# RGB_LED_Board.net
KiCad netlist of a schematic drawn in EAGLE
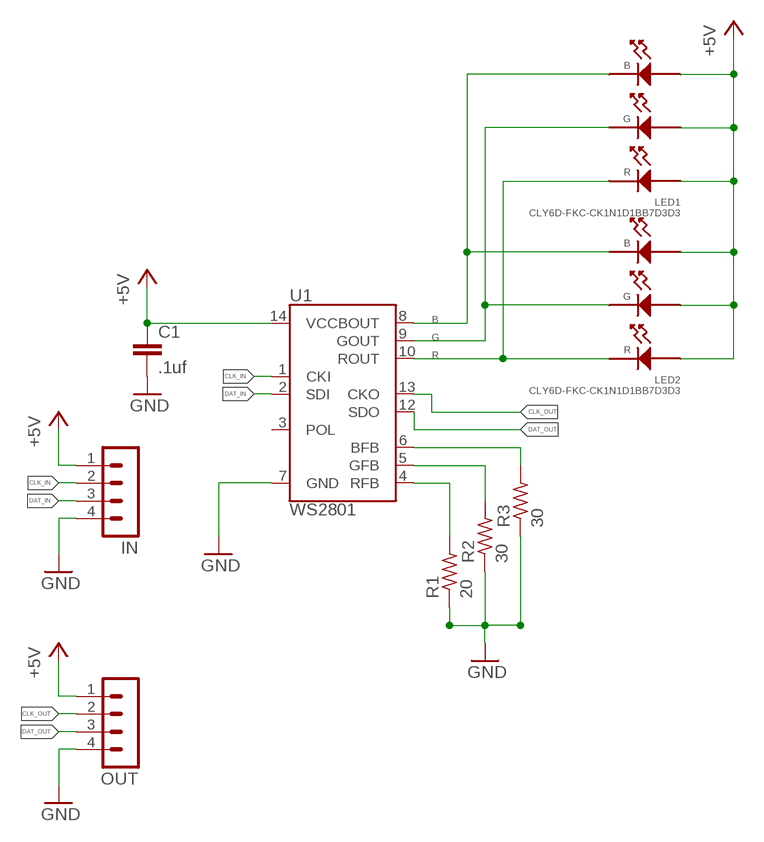
[diagram p0: schematic, sheet 1]

(export (version "E")
  (design (tool "Eeschema 10.0.6"))
  (components
    (comp (ref "C1")
      (value ".1uf")
      (footprint "eagle-import:0805")
      (libsource (lib "eagle-import") (part "CAP0805"))
    )
    (comp (ref "IN")
      (value "MA04-1")
      (footprint "eagle-import:MA04-1")
      (libsource (lib "eagle-import") (part "MA04-1"))
    )
    (comp (ref "LED1")
      (value "CLY6D-FKC-CK1N1D1BB7D3D3")
      (footprint "eagle-import:CLY6D-FKC")
      (libsource (lib "eagle-import") (part "CLY6D-FKC"))
    )
    (comp (ref "LED2")
      (value "CLY6D-FKC-CK1N1D1BB7D3D3")
      (footprint "eagle-import:CLY6D-FKC")
      (libsource (lib "eagle-import") (part "CLY6D-FKC"))
    )
    (comp (ref "OUT")
      (value "MA04-1")
      (footprint "eagle-import:MA04-1")
      (libsource (lib "eagle-import") (part "MA04-1"))
    )
    (comp (ref "R1")
      (value "20")
      (footprint "eagle-import:R0805")
      (libsource (lib "eagle-import") (part "R-US_R0805"))
    )
    (comp (ref "R2")
      (value "30")
      (footprint "eagle-import:R0805")
      (libsource (lib "eagle-import") (part "R-US_R0805"))
    )
    (comp (ref "R3")
      (value "30")
      (footprint "eagle-import:R0805")
      (libsource (lib "eagle-import") (part "R-US_R0805"))
    )
    (comp (ref "U1")
      (value "WS2801")
      (footprint "eagle-import:SOP-14")
      (libsource (lib "eagle-import") (part "WS2801"))
    )
  )
  (nets
    (net (code "1") (name "+5V") (class "Default")
      (node (ref "C1") (pin "1") (pinfunction "1_1") (pintype "passive"))
      (node (ref "IN") (pin "1") (pinfunction "1_1") (pintype "passive"))
      (node (ref "LED1") (pin "P$4") (pinfunction "ANODE_RED_P$4") (pintype "bidirectional"))
      (node (ref "LED1") (pin "P$5") (pinfunction "ANODE_GREEN_P$5") (pintype "bidirectional"))
      (node (ref "LED1") (pin "P$6") (pinfunction "ANODE_BLUE_P$6") (pintype "bidirectional"))
      (node (ref "LED2") (pin "P$4") (pinfunction "ANODE_RED_P$4") (pintype "bidirectional"))
      (node (ref "LED2") (pin "P$5") (pinfunction "ANODE_GREEN_P$5") (pintype "bidirectional"))
      (node (ref "LED2") (pin "P$6") (pinfunction "ANODE_BLUE_P$6") (pintype "bidirectional"))
      (node (ref "OUT") (pin "1") (pinfunction "1_1") (pintype "passive"))
      (node (ref "U1") (pin "14") (pinfunction "VCC_14") (pintype "bidirectional"))
    )
    (net (code "2") (name "/B") (class "Default")
      (node (ref "LED1") (pin "P$1") (pinfunction "CATHODE_BLUE_P$1") (pintype "bidirectional"))
      (node (ref "LED2") (pin "P$1") (pinfunction "CATHODE_BLUE_P$1") (pintype "bidirectional"))
      (node (ref "U1") (pin "8") (pinfunction "BOUT_8") (pintype "bidirectional"))
    )
    (net (code "3") (name "/G") (class "Default")
      (node (ref "LED1") (pin "P$2") (pinfunction "CATHODE_GREEN_P$2") (pintype "bidirectional"))
      (node (ref "LED2") (pin "P$2") (pinfunction "CATHODE_GREEN_P$2") (pintype "bidirectional"))
      (node (ref "U1") (pin "9") (pinfunction "GOUT_9") (pintype "bidirectional"))
    )
    (net (code "4") (name "/R") (class "Default")
      (node (ref "LED1") (pin "P$3") (pinfunction "CATHODE_RED_P$3") (pintype "bidirectional"))
      (node (ref "LED2") (pin "P$3") (pinfunction "CATHODE_RED_P$3") (pintype "bidirectional"))
      (node (ref "U1") (pin "10") (pinfunction "ROUT_10") (pintype "bidirectional"))
    )
    (net (code "5") (name "CLK_IN") (class "Default")
      (node (ref "IN") (pin "2") (pinfunction "2_2") (pintype "passive"))
      (node (ref "U1") (pin "1") (pinfunction "CKI_1") (pintype "bidirectional"))
    )
    (net (code "6") (name "CLK_OUT") (class "Default")
      (node (ref "OUT") (pin "2") (pinfunction "2_2") (pintype "passive"))
      (node (ref "U1") (pin "13") (pinfunction "CKO_13") (pintype "bidirectional"))
    )
    (net (code "7") (name "DAT_IN") (class "Default")
      (node (ref "IN") (pin "3") (pinfunction "3_3") (pintype "passive"))
      (node (ref "U1") (pin "2") (pinfunction "SDI_2") (pintype "bidirectional"))
    )
    (net (code "8") (name "DAT_OUT") (class "Default")
      (node (ref "OUT") (pin "3") (pinfunction "3_3") (pintype "passive"))
      (node (ref "U1") (pin "12") (pinfunction "SDO_12") (pintype "bidirectional"))
    )
    (net (code "9") (name "GND") (class "Default")
      (node (ref "C1") (pin "2") (pinfunction "2_2") (pintype "passive"))
      (node (ref "IN") (pin "4") (pinfunction "4_4") (pintype "passive"))
      (node (ref "OUT") (pin "4") (pinfunction "4_4") (pintype "passive"))
      (node (ref "R1") (pin "1") (pinfunction "1_1") (pintype "passive"))
      (node (ref "R2") (pin "1") (pinfunction "1_1") (pintype "passive"))
      (node (ref "R3") (pin "1") (pinfunction "1_1") (pintype "passive"))
      (node (ref "U1") (pin "7") (pinfunction "GND_7") (pintype "bidirectional"))
    )
    (net (code "10") (name "Net-(U1-BFB)") (class "Default")
      (node (ref "R3") (pin "2") (pinfunction "2_2") (pintype "passive"))
      (node (ref "U1") (pin "6") (pinfunction "BFB_6") (pintype "bidirectional"))
    )
    (net (code "11") (name "Net-(U1-GFB)") (class "Default")
      (node (ref "R2") (pin "2") (pinfunction "2_2") (pintype "passive"))
      (node (ref "U1") (pin "5") (pinfunction "GFB_5") (pintype "bidirectional"))
    )
    (net (code "12") (name "Net-(U1-RFB)") (class "Default")
      (node (ref "R1") (pin "2") (pinfunction "2_2") (pintype "passive"))
      (node (ref "U1") (pin "4") (pinfunction "RFB_4") (pintype "bidirectional"))
    )
    (net (code "13") (name "unconnected-(U1-POL-Pad3)") (class "Default")
      (node (ref "U1") (pin "3") (pinfunction "POL_3") (pintype "bidirectional"))
    )
  )
)
